# PCBA-2121-01.net
KiCad netlist of a schematic drawn in Altium Designer
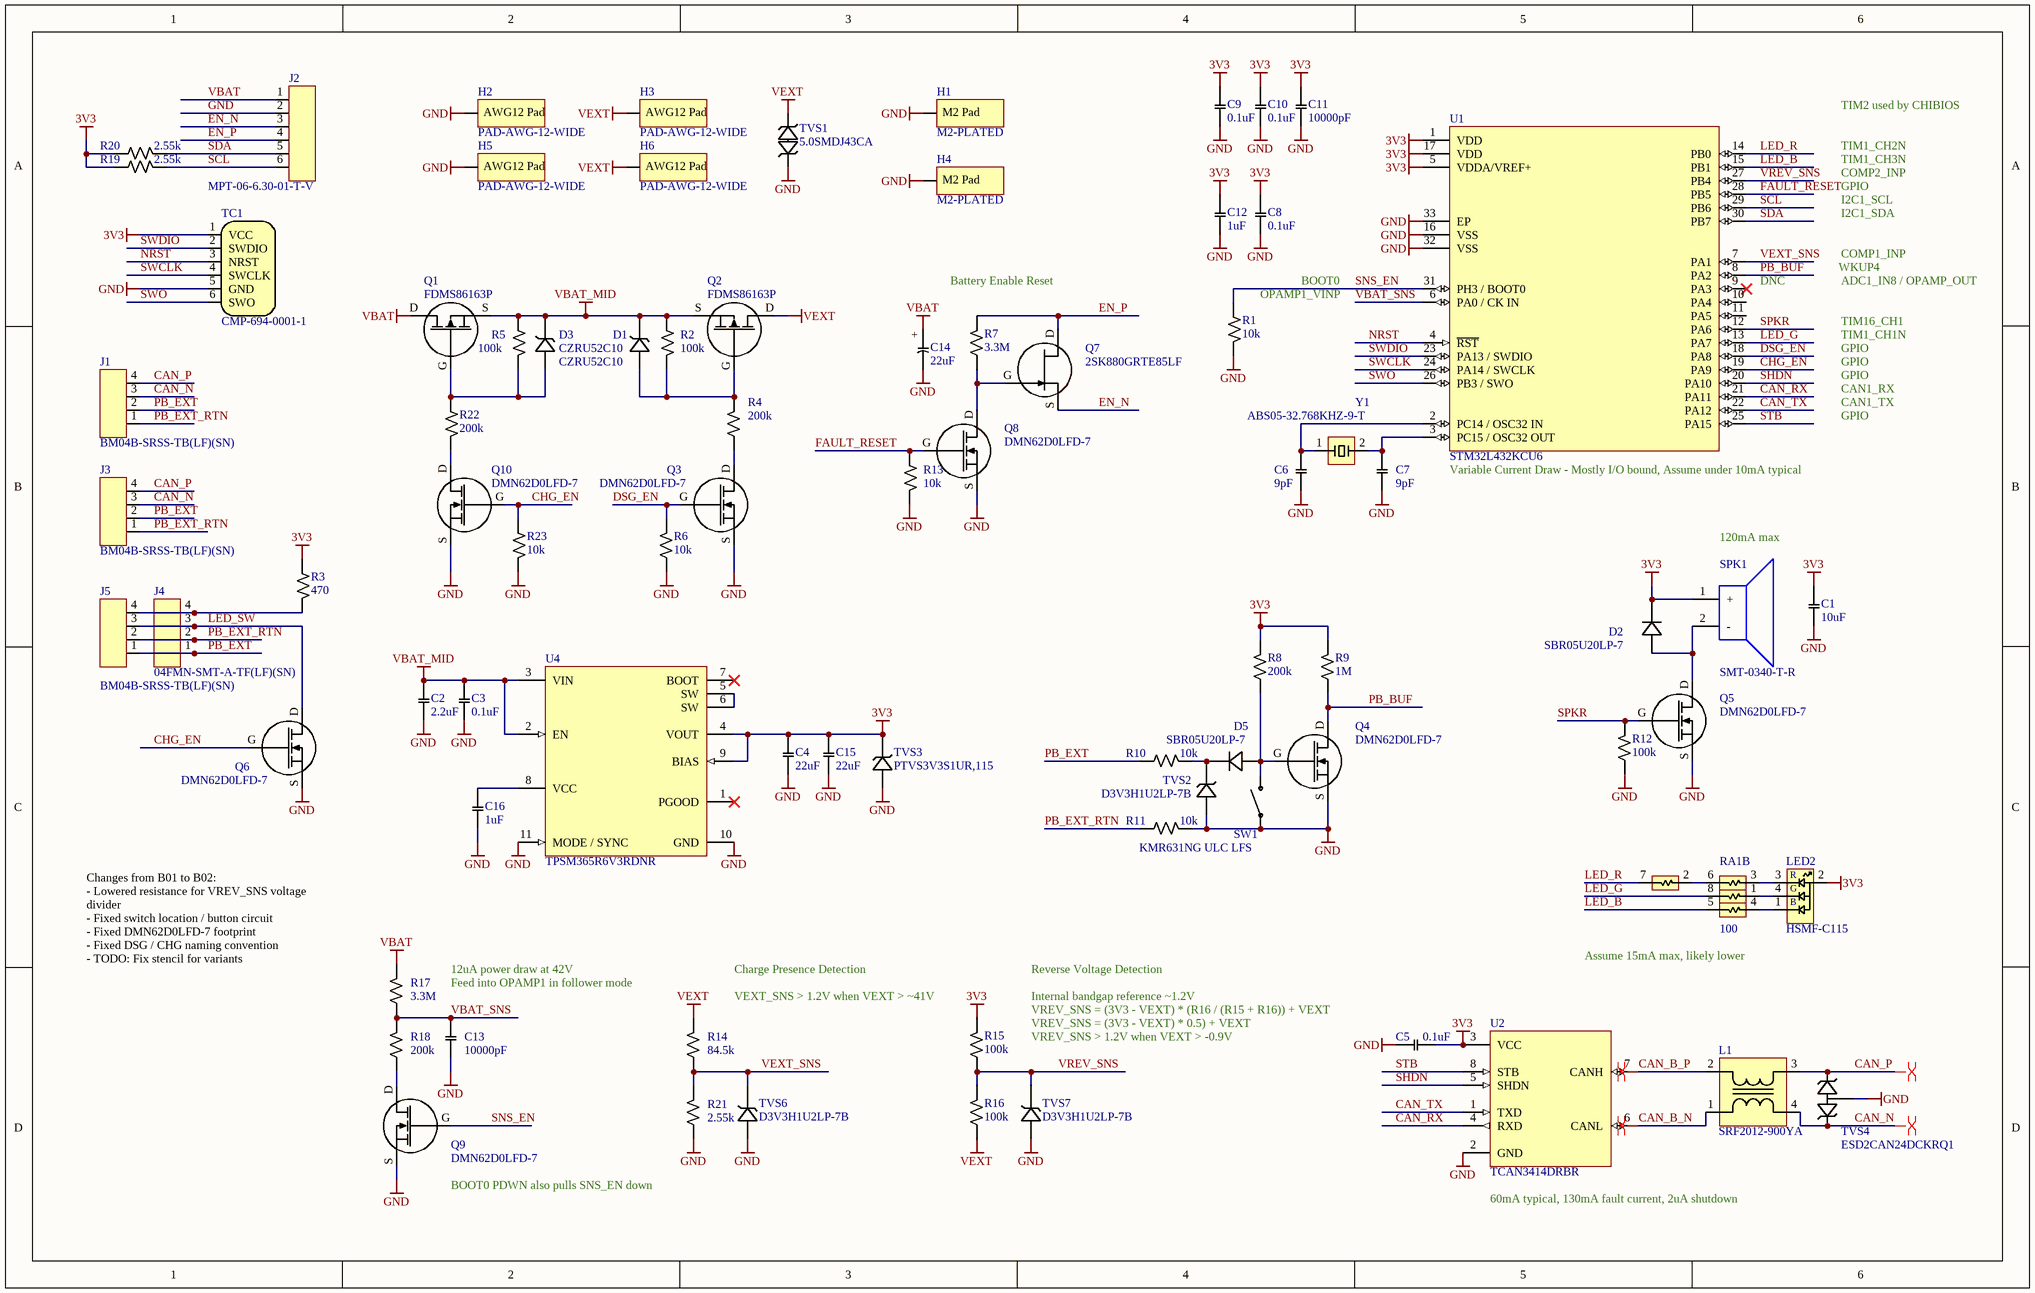
[diagram p0: PCBA-2121-01.SchDoc]

(export (version "E")
  (design (tool "Eeschema 10.0.6"))
  (components
    (comp (ref "C1")
      (value "C-10uf-X5R-16V-10%-0603")
      (footprint "C0603")
      (description "Capacitor Ceramic 10uF 16V X5R 10% SMD 0603")
      (fields (field (name "CAPACITANCE") "10uF") (field (name "TOLERANCE") "10%"))
      (libsource (lib "Hebi Robotics") (part "Capacitor"))
    )
    (comp (ref "C2")
      (value "C-2.2uf-X7R-100V-10%-1206")
      (footprint "C1206")
      (description "Capacitor Ceramic 2.2uF 100V X7R 10% SMD 1206")
      (fields (field (name "CAPACITANCE") "2.2uF") (field (name "TOLERANCE") "±10%"))
      (libsource (lib "Hebi Robotics") (part "Capacitor"))
    )
    (comp (ref "C3")
      (value "C-0.1uf-X7R-100V-10%-0603")
      (footprint "C0603")
      (description "Capacitor Ceramic 0.1uF 100V X7R 10% SMD 0603")
      (fields (field (name "CAPACITANCE") "0.1uF") (field (name "TOLERANCE") "±10%"))
      (libsource (lib "Hebi Robotics") (part "Capacitor"))
    )
    (comp (ref "C4")
      (value "C-22uf-X5R-25V-20%-1206")
      (footprint "C1206")
      (description "Capacitor Ceramic 22uF 25V X5R 20% SMD 1206")
      (fields (field (name "CAPACITANCE") "22uF") (field (name "TOLERANCE") "20%"))
      (libsource (lib "Hebi Robotics") (part "Capacitor"))
    )
    (comp (ref "C5")
      (value "C-0.1uf-X7R-25V-10%-0402")
      (footprint "C0402")
      (description "Capacitor Ceramic 0.1uF 25V X7R 10% SMD 0402")
      (fields (field (name "CAPACITANCE") "0.1uF") (field (name "TOLERANCE") "10%"))
      (libsource (lib "Hebi Robotics") (part "Capacitor"))
    )
    (comp (ref "C6")
      (value "C-9pf-NP0-50V-0.1pF-0402")
      (footprint "C0402")
      (description "Capacitor Ceramic 9pF 50V NP0 ±0.1pF SMD 0402")
      (fields (field (name "CAPACITANCE") "9pF") (field (name "TOLERANCE") "±0.1pF"))
      (libsource (lib "Hebi Robotics") (part "Capacitor"))
    )
    (comp (ref "C7")
      (value "C-9pf-NP0-50V-0.1pF-0402")
      (footprint "C0402")
      (description "Capacitor Ceramic 9pF 50V NP0 ±0.1pF SMD 0402")
      (fields (field (name "CAPACITANCE") "9pF") (field (name "TOLERANCE") "±0.1pF"))
      (libsource (lib "Hebi Robotics") (part "Capacitor"))
    )
    (comp (ref "C8")
      (value "C-0.1uf-X7R-25V-10%-0402")
      (footprint "C0402")
      (description "Capacitor Ceramic 0.1uF 25V X7R 10% SMD 0402")
      (fields (field (name "CAPACITANCE") "0.1uF") (field (name "TOLERANCE") "10%"))
      (libsource (lib "Hebi Robotics") (part "Capacitor"))
    )
    (comp (ref "C9")
      (value "C-0.1uf-X7R-25V-10%-0402")
      (footprint "C0402")
      (description "Capacitor Ceramic 0.1uF 25V X7R 10% SMD 0402")
      (fields (field (name "CAPACITANCE") "0.1uF") (field (name "TOLERANCE") "10%"))
      (libsource (lib "Hebi Robotics") (part "Capacitor"))
    )
    (comp (ref "C10")
      (value "C-0.1uf-X7R-25V-10%-0402")
      (footprint "C0402")
      (description "Capacitor Ceramic 0.1uF 25V X7R 10% SMD 0402")
      (fields (field (name "CAPACITANCE") "0.1uF") (field (name "TOLERANCE") "10%"))
      (libsource (lib "Hebi Robotics") (part "Capacitor"))
    )
    (comp (ref "C11")
      (value "C-10000pf-X7R-50V-10%-0402")
      (footprint "C0402")
      (description "Capacitor Ceramic 10000pF 50V X7R 10% SMD 0402")
      (fields (field (name "TOLERANCE") "10%") (field (name "CAPACITANCE") "10000pF"))
      (libsource (lib "Hebi Robotics") (part "Capacitor"))
    )
    (comp (ref "C12")
      (value "C-1uf-X5R-25V-10%-0402")
      (footprint "C0402")
      (description "Capacitor Ceramic 1uF 25V X5R 10% SMD 0402")
      (fields (field (name "CAPACITANCE") "1uF") (field (name "TOLERANCE") "±10%"))
      (libsource (lib "Hebi Robotics") (part "Capacitor"))
    )
    (comp (ref "C13")
      (value "C-10000pf-X7R-50V-10%-0402")
      (footprint "C0402")
      (description "Capacitor Ceramic 10000pF 50V X7R 10% SMD 0402")
      (fields (field (name "CAPACITANCE") "10000pF") (field (name "TOLERANCE") "10%"))
      (libsource (lib "Hebi Robotics") (part "Capacitor"))
    )
    (comp (ref "C14")
      (value "UCM1H220MCL1GS")
      (footprint "CAPAE5753X61L")
      (description "CAP ALUM 22UF 20% 50V SMD")
      (fields
        (field (name "CAPACITANCE") "22uF")
        (field (name "TOLERANCE") "20%")
        (field (name "VOLTAGE") "50V")
      )
      (libsource (lib "Hebi Robotics") (part "Capacitor_Polarized"))
    )
    (comp (ref "C15")
      (value "C-22uf-X5R-25V-20%-1206")
      (footprint "C1206")
      (description "Capacitor Ceramic 22uF 25V X5R 20% SMD 1206")
      (fields (field (name "CAPACITANCE") "22uF") (field (name "TOLERANCE") "20%"))
      (libsource (lib "Hebi Robotics") (part "Capacitor"))
    )
    (comp (ref "C16")
      (value "C-1uf-X5R-25V-10%-0402")
      (footprint "C0402")
      (description "Capacitor Ceramic 1uF 25V X5R 10% SMD 0402")
      (fields (field (name "CAPACITANCE") "1uF") (field (name "TOLERANCE") "±10%"))
      (libsource (lib "Hebi Robotics") (part "Capacitor"))
    )
    (comp (ref "D1")
      (value "CZRU52C10")
      (footprint "CZRU52C10")
      (description "DIODE ZENER 10V 150MW 0603")
      (libsource (lib "Hebi Robotics") (part "ZENER"))
    )
    (comp (ref "D2")
      (value "SBR05U20LP-7")
      (footprint "DFN1006-2_DIODES")
      (description "DIODE SBR 20V 500MA 2DFN")
      (libsource (lib "Hebi Robotics") (part "DIODE"))
    )
    (comp (ref "D3")
      (value "CZRU52C10")
      (footprint "CZRU52C10")
      (description "DIODE ZENER 10V 150MW 0603")
      (libsource (lib "Hebi Robotics") (part "ZENER"))
    )
    (comp (ref "D5")
      (value "SBR05U20LP-7")
      (footprint "DFN1006-2_DIODES")
      (description "DIODE SBR 20V 500MA 2DFN")
      (libsource (lib "Hebi Robotics") (part "DIODE"))
    )
    (comp (ref "H1")
      (value "M2-PLATED")
      (footprint "M2-PLATED-NORMAL")
      (description "M2 Size Screw Hole, Normal Fit, Plated")
      (libsource (lib "Hebi Robotics") (part "MOUNTING_HOLE"))
    )
    (comp (ref "H2")
      (value "PAD-AWG-12-WIDE")
      (footprint "AWG-12-With-Wire")
      (description "AWG 12 Hole with Wider Pad")
      (libsource (lib "Hebi Robotics") (part "WIRE_PAD"))
    )
    (comp (ref "H3")
      (value "PAD-AWG-12-WIDE")
      (footprint "AWG-12-With-Wire")
      (description "AWG 12 Hole with Wider Pad")
      (libsource (lib "Hebi Robotics") (part "WIRE_PAD"))
    )
    (comp (ref "H4")
      (value "M2-PLATED")
      (footprint "M2-PLATED-NORMAL")
      (description "M2 Size Screw Hole, Normal Fit, Plated")
      (libsource (lib "Hebi Robotics") (part "MOUNTING_HOLE"))
    )
    (comp (ref "H5")
      (value "PAD-AWG-12-WIDE")
      (footprint "AWG-12-With-Wire")
      (description "AWG 12 Hole with Wider Pad")
      (libsource (lib "Hebi Robotics") (part "WIRE_PAD"))
    )
    (comp (ref "H6")
      (value "PAD-AWG-12-WIDE")
      (footprint "AWG-12-With-Wire")
      (description "AWG 12 Hole with Wider Pad")
      (libsource (lib "Hebi Robotics") (part "WIRE_PAD"))
    )
    (comp (ref "J1")
      (value "BM04B-SRSS-TB(LF)(SN)")
      (footprint "BM04B-SRSS-TB")
      (description "CONN HEADER SH 4POS TOP 1MM TIN")
      (fields (field (name "MANUFACTURER") "JST Sales America Inc"))
      (libsource (lib "Hebi Robotics") (part "CONN_1_ROW_004_POS"))
    )
    (comp (ref "J2")
      (value "MPT-06-6.30-01-T-V")
      (footprint "MPT-06-6.30-01-T-V-Footprint-1")
      (description "5.00 MM POWERSTRIP/30 A DUAL BL")
      (libsource (lib "Hebi Robotics") (part "CONN_1_ROW_006_POS"))
    )
    (comp (ref "J3")
      (value "BM04B-SRSS-TB(LF)(SN)")
      (footprint "BM04B-SRSS-TB")
      (description "CONN HEADER SH 4POS TOP 1MM TIN")
      (fields (field (name "MANUFACTURER") "JST Sales America Inc"))
      (libsource (lib "Hebi Robotics") (part "CONN_1_ROW_004_POS"))
    )
    (comp (ref "J4")
      (value "04FMN-SMT-A-TF(LF)(SN)")
      (footprint "04FMN-SMT-A-TF(LF)(SN)-Footprint-1")
      (description "Ffc / Fpc Board Connector, Fmn Series, Surface Mount, Receptacle, 4, 1 Mm Rohs Compliant: Yes")
      (libsource (lib "Hebi Robotics") (part "CONN_1_ROW_004_POS"))
    )
    (comp (ref "J5")
      (value "BM04B-SRSS-TB(LF)(SN)")
      (footprint "BM04B-SRSS-TB")
      (description "CONN HEADER SH 4POS TOP 1MM TIN")
      (fields (field (name "MANUFACTURER") "JST Sales America Inc"))
      (libsource (lib "Hebi Robotics") (part "CONN_1_ROW_004_POS"))
    )
    (comp (ref "L1")
      (value "SRF2012-900YA")
      (footprint "FP-SRF2012A-MFG")
      (description "CMC 400MA 2LN 90 OHM SMD")
      (libsource (lib "Hebi Robotics") (part "CM_CHOKE_4PIN"))
    )
    (comp (ref "LED2")
      (value "HSMF-C115")
      (footprint "HSMF-C115")
      (description "LED RGB DIFFUSED CHIP SMD R/A")
      (libsource (lib "Hebi Robotics") (part "HSMF-C115"))
    )
    (comp (ref "Q1")
      (value "FDMS86163P")
      (footprint "FDMS86300DC")
      (description "MOSFET P-CH 100V 7.9A POWER56")
      (libsource (lib "Hebi Robotics") (part "P_MOSFET"))
    )
    (comp (ref "Q2")
      (value "FDMS86163P")
      (footprint "FDMS86300DC")
      (description "MOSFET P-CH 100V 7.9A POWER56")
      (libsource (lib "Hebi Robotics") (part "P_MOSFET"))
    )
    (comp (ref "Q3")
      (value "DMN62D0LFD-7")
      (footprint "DMN62D0LFD-7-Footprint-1")
      (description "MOSFET N-CH 60V 310MA 3DFN")
      (libsource (lib "Hebi Robotics") (part "N_MOSFET"))
    )
    (comp (ref "Q4")
      (value "DMN62D0LFD-7")
      (footprint "DMN62D0LFD-7-Footprint-1")
      (description "MOSFET N-CH 60V 310MA 3DFN")
      (libsource (lib "Hebi Robotics") (part "N_MOSFET"))
    )
    (comp (ref "Q5")
      (value "DMN62D0LFD-7")
      (footprint "DMN62D0LFD-7-Footprint-1")
      (description "MOSFET N-CH 60V 310MA 3DFN")
      (libsource (lib "Hebi Robotics") (part "N_MOSFET"))
    )
    (comp (ref "Q6")
      (value "DMN62D0LFD-7")
      (footprint "DMN62D0LFD-7-Footprint-1")
      (description "MOSFET N-CH 60V 310MA 3DFN")
      (libsource (lib "Hebi Robotics") (part "N_MOSFET"))
    )
    (comp (ref "Q7")
      (value "2SK880GRTE85LF")
      (footprint "SOT65P205X100-3L")
      (description "JFET N-CH 50V SC70")
      (libsource (lib "Hebi Robotics") (part "N_JFET"))
    )
    (comp (ref "Q8")
      (value "DMN62D0LFD-7")
      (footprint "DMN62D0LFD-7-Footprint-1")
      (description "MOSFET N-CH 60V 310MA 3DFN")
      (libsource (lib "Hebi Robotics") (part "N_MOSFET"))
    )
    (comp (ref "Q9")
      (value "DMN62D0LFD-7")
      (footprint "DMN62D0LFD-7-Footprint-1")
      (description "MOSFET N-CH 60V 310MA 3DFN")
      (libsource (lib "Hebi Robotics") (part "N_MOSFET"))
    )
    (comp (ref "Q10")
      (value "DMN62D0LFD-7")
      (footprint "DMN62D0LFD-7-Footprint-1")
      (description "MOSFET N-CH 60V 310MA 3DFN")
      (libsource (lib "Hebi Robotics") (part "N_MOSFET"))
    )
    (comp (ref "R1")
      (value "R-10k-1%-0.063w-0402")
      (footprint "R0402")
      (description "Resistor 0402 10k Ohm 1% 1-16 Watt")
      (fields
        (field (name "POWER") "0.063W, 1/16W")
        (field (name "RESISTANCE") "10k")
        (field (name "TOLERANCE") "1%")
      )
      (libsource (lib "Hebi Robotics") (part "Resistor"))
    )
    (comp (ref "R2")
      (value "R-100k-1%-0.063w-0402")
      (footprint "R0402")
      (description "Resistor 0402 100k Ohm 1% 1-16 Watt")
      (fields
        (field (name "POWER") "0.063W, 1/16W")
        (field (name "RESISTANCE") "100k")
        (field (name "TOLERANCE") "1%")
      )
      (libsource (lib "Hebi Robotics") (part "Resistor"))
    )
    (comp (ref "R3")
      (value "R-470-1%-0.063w-0402")
      (footprint "R0402")
      (description "Resistor 0402 470 Ohm 1% 1-16 Watt")
      (fields
        (field (name "POWER") "0.063W, 1/16W")
        (field (name "TOLERANCE") "1%")
        (field (name "RESISTANCE") "470")
      )
      (libsource (lib "Hebi Robotics") (part "Resistor"))
    )
    (comp (ref "R4")
      (value "R-200k-1%-0.063w-0402")
      (footprint "R0402")
      (description "Resistor 0402 200k Ohm 1% 1-16 Watt")
      (fields
        (field (name "POWER") "0.063W, 1/16W")
        (field (name "RESISTANCE") "200k")
        (field (name "TOLERANCE") "1%")
      )
      (libsource (lib "Hebi Robotics") (part "Resistor"))
    )
    (comp (ref "R5")
      (value "R-100k-1%-0.063w-0402")
      (footprint "R0402")
      (description "Resistor 0402 100k Ohm 1% 1-16 Watt")
      (fields
        (field (name "POWER") "0.063W, 1/16W")
        (field (name "RESISTANCE") "100k")
        (field (name "TOLERANCE") "1%")
      )
      (libsource (lib "Hebi Robotics") (part "Resistor"))
    )
    (comp (ref "R6")
      (value "R-10k-1%-0.063w-0402")
      (footprint "R0402")
      (description "Resistor 0402 10k Ohm 1% 1-16 Watt")
      (fields
        (field (name "POWER") "0.063W, 1/16W")
        (field (name "RESISTANCE") "10k")
        (field (name "TOLERANCE") "1%")
      )
      (libsource (lib "Hebi Robotics") (part "Resistor"))
    )
    (comp (ref "R7")
      (value "R-3.3M-1%-0.063w-0402")
      (footprint "R0402")
      (description "Resistor 0402 3.3M Ohm 1% 1-16 Watt")
      (fields (field (name "POWER") "0.063W, 1/16W") (field (name "RESISTANCE") "3.3M"))
      (libsource (lib "Hebi Robotics") (part "Resistor"))
    )
    (comp (ref "R8")
      (value "R-200k-1%-0.063w-0402")
      (footprint "R0402")
      (description "Resistor 0402 200k Ohm 1% 1-16 Watt")
      (fields
        (field (name "RESISTANCE") "200k")
        (field (name "POWER") "0.063W, 1/16W")
        (field (name "TOLERANCE") "1%")
      )
      (libsource (lib "Hebi Robotics") (part "Resistor"))
    )
    (comp (ref "R9")
      (value "R-1M-1%-0.063w-0402")
      (footprint "R0402")
      (description "Resistor 0402 1M Ohm 1% 1-16 Watt")
      (fields
        (field (name "RESISTANCE") "1M")
        (field (name "POWER") "0.063W, 1/16W")
        (field (name "TOLERANCE") "1%")
      )
      (libsource (lib "Hebi Robotics") (part "Resistor"))
    )
    (comp (ref "R10")
      (value "R-10k-1%-0.063w-0402")
      (footprint "R0402")
      (description "Resistor 0402 10k Ohm 1% 1-16 Watt")
      (fields
        (field (name "POWER") "0.063W, 1/16W")
        (field (name "RESISTANCE") "10k")
        (field (name "TOLERANCE") "1%")
      )
      (libsource (lib "Hebi Robotics") (part "Resistor"))
    )
    (comp (ref "R11")
      (value "R-10k-1%-0.063w-0402")
      (footprint "R0402")
      (description "Resistor 0402 10k Ohm 1% 1-16 Watt")
      (fields
        (field (name "POWER") "0.063W, 1/16W")
        (field (name "RESISTANCE") "10k")
        (field (name "TOLERANCE") "1%")
      )
      (libsource (lib "Hebi Robotics") (part "Resistor"))
    )
    (comp (ref "R12")
      (value "R-100k-1%-0.063w-0402")
      (footprint "R0402")
      (description "Resistor 0402 100k Ohm 1% 1-16 Watt")
      (fields
        (field (name "POWER") "0.063W, 1/16W")
        (field (name "TOLERANCE") "1%")
        (field (name "RESISTANCE") "100k")
      )
      (libsource (lib "Hebi Robotics") (part "Resistor"))
    )
    (comp (ref "R13")
      (value "R-10k-1%-0.063w-0402")
      (footprint "R0402")
      (description "Resistor 0402 10k Ohm 1% 1-16 Watt")
      (fields
        (field (name "POWER") "0.063W, 1/16W")
        (field (name "RESISTANCE") "10k")
        (field (name "TOLERANCE") "1%")
      )
      (libsource (lib "Hebi Robotics") (part "Resistor"))
    )
    (comp (ref "R14")
      (value "R-84.5k-1%-0.063w-0402")
      (footprint "R0402")
      (description "Resistor 0402 84.5k Ohm 1% 1-16 Watt")
      (fields (field (name "RESISTANCE") "84.5k") (field (name "POWER") "0.063W, 1/16W"))
      (libsource (lib "Hebi Robotics") (part "Resistor"))
    )
    (comp (ref "R15")
      (value "R-100k-1%-0.063w-0402")
      (footprint "R0402")
      (description "Resistor 0402 100k Ohm 1% 1-16 Watt")
      (fields
        (field (name "POWER") "0.063W, 1/16W")
        (field (name "RESISTANCE") "100k")
        (field (name "TOLERANCE") "1%")
      )
      (libsource (lib "Hebi Robotics") (part "Resistor"))
    )
    (comp (ref "R16")
      (value "R-100k-1%-0.063w-0402")
      (footprint "R0402")
      (description "Resistor 0402 100k Ohm 1% 1-16 Watt")
      (fields
        (field (name "POWER") "0.063W, 1/16W")
        (field (name "RESISTANCE") "100k")
        (field (name "TOLERANCE") "1%")
      )
      (libsource (lib "Hebi Robotics") (part "Resistor"))
    )
    (comp (ref "R17")
      (value "R-3.3M-1%-0.063w-0402")
      (footprint "R0402")
      (description "Resistor 0402 3.3M Ohm 1% 1-16 Watt")
      (fields (field (name "POWER") "0.063W, 1/16W") (field (name "RESISTANCE") "3.3M"))
      (libsource (lib "Hebi Robotics") (part "Resistor"))
    )
    (comp (ref "R18")
      (value "R-200k-1%-0.063w-0402")
      (footprint "R0402")
      (description "Resistor 0402 200k Ohm 1% 1-16 Watt")
      (fields
        (field (name "POWER") "0.063W, 1/16W")
        (field (name "RESISTANCE") "200k")
        (field (name "TOLERANCE") "1%")
      )
      (libsource (lib "Hebi Robotics") (part "Resistor"))
    )
    (comp (ref "R19")
      (value "R-2.55k-1%-0.063w-0402")
      (footprint "R0402")
      (description "Resistor 0402 2.55k Ohm 1% 1-16 Watt")
      (fields (field (name "RESISTANCE") "2.55k") (field (name "POWER") "0.063W, 1/16W"))
      (libsource (lib "Hebi Robotics") (part "Resistor"))
    )
    (comp (ref "R20")
      (value "R-2.55k-1%-0.063w-0402")
      (footprint "R0402")
      (description "Resistor 0402 2.55k Ohm 1% 1-16 Watt")
      (fields (field (name "RESISTANCE") "2.55k") (field (name "POWER") "0.063W, 1/16W"))
      (libsource (lib "Hebi Robotics") (part "Resistor"))
    )
    (comp (ref "R21")
      (value "R-2.55k-1%-0.063w-0402")
      (footprint "R0402")
      (description "Resistor 0402 2.55k Ohm 1% 1-16 Watt")
      (fields (field (name "POWER") "0.063W, 1/16W") (field (name "RESISTANCE") "2.55k"))
      (libsource (lib "Hebi Robotics") (part "Resistor"))
    )
    (comp (ref "R22")
      (value "R-200k-1%-0.063w-0402")
      (footprint "R0402")
      (description "Resistor 0402 200k Ohm 1% 1-16 Watt")
      (fields
        (field (name "POWER") "0.063W, 1/16W")
        (field (name "RESISTANCE") "200k")
        (field (name "TOLERANCE") "1%")
      )
      (libsource (lib "Hebi Robotics") (part "Resistor"))
    )
    (comp (ref "R23")
      (value "R-10k-1%-0.063w-0402")
      (footprint "R0402")
      (description "Resistor 0402 10k Ohm 1% 1-16 Watt")
      (fields
        (field (name "POWER") "0.063W, 1/16W")
        (field (name "RESISTANCE") "10k")
        (field (name "TOLERANCE") "1%")
      )
      (libsource (lib "Hebi Robotics") (part "Resistor"))
    )
    (comp (ref "RA1")
      (value "RA-4-C-100-5%-0.063w-0804")
      (footprint "741C083")
      (description "100 ohm Resistor Array 4 Element Concave 5%  1-16Watt 0804")
      (fields (field (name "POWER") "0.063W") (field (name "RESISTANCE") "100"))
      (libsource (lib "Hebi Robotics") (part "RA4"))
    )
    (comp (ref "SPK1")
      (value "SMT-0340-T-R")
      (footprint "SMT-0340-T-R")
      (description "BUZZER MAGNETIC 3V 3.2X3.2MM SMD")
      (fields (field (name "VOLTAGE") "3V"))
      (libsource (lib "Hebi Robotics") (part "Speaker"))
    )
    (comp (ref "SW1")
      (value "KMR631NG ULC LFS")
      (footprint "KMR6_CK")
      (description "SWITCH TACTILE SPST-NO 50MA 32V")
      (fields (field (name "MANUFACTURER") "ITT C&K"))
      (libsource (lib "Hebi Robotics") (part "SPST_NO"))
    )
    (comp (ref "TC1")
      (value "CMP-694-0001-1")
      (footprint "TC2030-MCP-NL_SMALL")
      (description "TC2030-MCP-NL")
      (fields (field (name "MANUFACTURER PART NUMBER") "TC2030-MCP-NL_SMALL"))
      (libsource (lib "Hebi Robotics") (part "TC2030-MCP-NL"))
    )
    (comp (ref "TVS1")
      (value "5.0SMDJ43CA")
      (footprint "DIOM6959X26L")
      (description "TVS DIODE 43VWM 69.4VC DO214AB")
      (libsource (lib "Hebi Robotics") (part "TVS_BI"))
    )
    (comp (ref "TVS2")
      (value "D3V3H1U2LP-7B")
      (footprint "DFN70P101X53-2N")
      (description "TVS DIODE 3.3V 10V DFN1006-2")
      (libsource (lib "Hebi Robotics") (part "TVS"))
    )
    (comp (ref "TVS3")
      (value "PTVS3V3S1UR,115")
      (footprint "SOD-123W_NXP")
      (description "TVS DIODE 3.3VWM 8VC SOD123W")
      (libsource (lib "Hebi Robotics") (part "TVS"))
    )
    (comp (ref "TVS4")
      (value "ESD2CAN24DCKRQ1")
      (footprint "SOT65P210X90-3L")
      (description "TVS DIODE 24VWM 37VC CAN SC703")
      (libsource (lib "Hebi Robotics") (part "ESD2CAN24DCKRQ1-Symbol-1"))
    )
    (comp (ref "TVS6")
      (value "D3V3H1U2LP-7B")
      (footprint "DFN70P101X53-2N")
      (description "TVS DIODE 3.3V 10V DFN1006-2")
      (libsource (lib "Hebi Robotics") (part "TVS"))
    )
    (comp (ref "TVS7")
      (value "D3V3H1U2LP-7B")
      (footprint "DFN70P101X53-2N")
      (description "TVS DIODE 3.3V 10V DFN1006-2")
      (libsource (lib "Hebi Robotics") (part "TVS"))
    )
    (comp (ref "U1")
      (value "STM32L432KCU6")
      (footprint "QFN50P500X500X60_HS-33L")
      (description "IC MCU 32BIT 256KB FLSH 32UFQFPN")
      (libsource (lib "Hebi Robotics") (part "STM32L412K8U6"))
    )
    (comp (ref "U2")
      (value "TCAN3414DRBR")
      (footprint "SON65P300X100_HS-9L")
      (description "IC TRANSCEIVER HALF 1/1 8SON")
      (libsource (lib "Hebi Robotics") (part "TCAN3414DRBR-Symbol-1"))
    )
    (comp (ref "U4")
      (value "TPSM365R6V3RDNR")
      (footprint "TPSM365R6V3RDNR-Footprint-1")
      (description "3-V TO 65-V INPUT, 3V3 OUT, 300mA")
      (libsource (lib "Hebi Robotics") (part "TPSM365R6V3RDNR-Symbol-1"))
    )
    (comp (ref "Y1")
      (value "ABS05-32.768KHZ-9-T")
      (footprint "ABS05-32.768KHZ-9-T-Footprint-1")
      (description "CRYSTAL 32.7680KHZ 9PF SMD")
      (libsource (lib "Hebi Robotics") (part "CRYSTAL"))
    )
  )
  (nets
    (net (code "1") (name "/CAN_B_N") (class "Default")
      (node (ref "L1") (pin "1") (pinfunction "1_1") (pintype "passive"))
      (node (ref "U2") (pin "6") (pinfunction "CANL_6") (pintype "bidirectional"))
    )
    (net (code "2") (name "/CAN_B_P") (class "Default")
      (node (ref "L1") (pin "2") (pinfunction "2_2") (pintype "passive"))
      (node (ref "U2") (pin "7") (pinfunction "CANH_7") (pintype "bidirectional"))
    )
    (net (code "3") (name "/CAN_N") (class "Default")
      (node (ref "J1") (pin "3") (pinfunction "3_3") (pintype "passive"))
      (node (ref "J3") (pin "3") (pinfunction "3_3") (pintype "passive"))
      (node (ref "L1") (pin "4") (pinfunction "4_4") (pintype "passive"))
      (node (ref "TVS4") (pin "2") (pinfunction "2_2") (pintype "passive"))
    )
    (net (code "4") (name "/CAN_P") (class "Default")
      (node (ref "J1") (pin "4") (pinfunction "4_4") (pintype "passive"))
      (node (ref "J3") (pin "4") (pinfunction "4_4") (pintype "passive"))
      (node (ref "L1") (pin "3") (pinfunction "3_3") (pintype "passive"))
      (node (ref "TVS4") (pin "1") (pinfunction "1_1") (pintype "passive"))
    )
    (net (code "5") (name "/CAN_RX") (class "Default")
      (node (ref "U1") (pin "21") (pinfunction "PA11_21") (pintype "bidirectional"))
      (node (ref "U2") (pin "4") (pinfunction "RXD_4") (pintype "output"))
    )
    (net (code "6") (name "/CAN_TX") (class "Default")
      (node (ref "U1") (pin "22") (pinfunction "PA12_22") (pintype "bidirectional"))
      (node (ref "U2") (pin "1") (pinfunction "TXD_1") (pintype "input"))
    )
    (net (code "7") (name "/CHG_EN") (class "Default")
      (node (ref "Q10") (pin "G") (pinfunction "G_G") (pintype "passive"))
      (node (ref "Q6") (pin "G") (pinfunction "G_G") (pintype "passive"))
      (node (ref "R23") (pin "2") (pinfunction "2_2") (pintype "passive"))
      (node (ref "U1") (pin "19") (pinfunction "PA9_19") (pintype "bidirectional"))
    )
    (net (code "8") (name "/DSG_EN") (class "Default")
      (node (ref "Q3") (pin "G") (pinfunction "G_G") (pintype "passive"))
      (node (ref "R6") (pin "2") (pinfunction "2_2") (pintype "passive"))
      (node (ref "U1") (pin "18") (pinfunction "PA8_18") (pintype "bidirectional"))
    )
    (net (code "9") (name "/EN_N") (class "Default")
      (node (ref "J2") (pin "3") (pinfunction "3_3") (pintype "passive"))
      (node (ref "Q7") (pin "S") (pinfunction "S_S") (pintype "passive"))
    )
    (net (code "10") (name "/EN_P") (class "Default")
      (node (ref "J2") (pin "4") (pinfunction "4_4") (pintype "passive"))
      (node (ref "Q7") (pin "D") (pinfunction "D_D") (pintype "passive"))
      (node (ref "R7") (pin "2") (pinfunction "2_2") (pintype "passive"))
    )
    (net (code "11") (name "/FAULT_RESET") (class "Default")
      (node (ref "Q8") (pin "G") (pinfunction "G_G") (pintype "passive"))
      (node (ref "R13") (pin "1") (pinfunction "1_1") (pintype "passive"))
      (node (ref "U1") (pin "28") (pinfunction "PB5_28") (pintype "bidirectional"))
    )
    (net (code "12") (name "/LED_B") (class "Default")
      (node (ref "RA1") (pin "5") (pinfunction "5_5") (pintype "passive"))
      (node (ref "U1") (pin "15") (pinfunction "PB1_15") (pintype "bidirectional"))
    )
    (net (code "13") (name "/LED_G") (class "Default")
      (node (ref "RA1") (pin "8") (pinfunction "8_8") (pintype "passive"))
      (node (ref "U1") (pin "13") (pinfunction "PA7_13") (pintype "bidirectional"))
    )
    (net (code "14") (name "/LED_R") (class "Default")
      (node (ref "RA1") (pin "7") (pinfunction "7_7") (pintype "passive"))
      (node (ref "U1") (pin "14") (pinfunction "PB0_14") (pintype "bidirectional"))
    )
    (net (code "15") (name "/LED_SW") (class "Default")
      (node (ref "J4") (pin "3") (pinfunction "3_3") (pintype "passive"))
      (node (ref "J5") (pin "3") (pinfunction "3_3") (pintype "passive"))
      (node (ref "Q6") (pin "D") (pinfunction "D_D") (pintype "passive"))
    )
    (net (code "16") (name "/NRST") (class "Default")
      (node (ref "TC1") (pin "3") (pinfunction "NRST_3") (pintype "passive"))
      (node (ref "U1") (pin "4") (pinfunction "~{RST}_4") (pintype "input"))
    )
    (net (code "17") (name "/PB_BUF") (class "Default")
      (node (ref "Q4") (pin "D") (pinfunction "D_D") (pintype "passive"))
      (node (ref "R9") (pin "1") (pinfunction "1_1") (pintype "passive"))
      (node (ref "U1") (pin "8") (pinfunction "PA2_8") (pintype "bidirectional"))
    )
    (net (code "18") (name "/PB_EXT") (class "Default")
      (node (ref "J1") (pin "2") (pinfunction "2_2") (pintype "passive"))
      (node (ref "J3") (pin "2") (pinfunction "2_2") (pintype "passive"))
      (node (ref "J4") (pin "1") (pinfunction "1_1") (pintype "passive"))
      (node (ref "J5") (pin "1") (pinfunction "1_1") (pintype "passive"))
      (node (ref "R10") (pin "1") (pinfunction "1_1") (pintype "passive"))
    )
    (net (code "19") (name "/PB_EXT_RTN") (class "Default")
      (node (ref "J1") (pin "1") (pinfunction "1_1") (pintype "passive"))
      (node (ref "J3") (pin "1") (pinfunction "1_1") (pintype "passive"))
      (node (ref "J4") (pin "2") (pinfunction "2_2") (pintype "passive"))
      (node (ref "J5") (pin "2") (pinfunction "2_2") (pintype "passive"))
      (node (ref "R11") (pin "1") (pinfunction "1_1") (pintype "passive"))
    )
    (net (code "20") (name "/SCL") (class "Default")
      (node (ref "J2") (pin "6") (pinfunction "6_6") (pintype "passive"))
      (node (ref "R19") (pin "2") (pinfunction "2_2") (pintype "passive"))
      (node (ref "U1") (pin "29") (pinfunction "PB6_29") (pintype "bidirectional"))
    )
    (net (code "21") (name "/SDA") (class "Default")
      (node (ref "J2") (pin "5") (pinfunction "5_5") (pintype "passive"))
      (node (ref "R20") (pin "2") (pinfunction "2_2") (pintype "passive"))
      (node (ref "U1") (pin "30") (pinfunction "PB7_30") (pintype "bidirectional"))
    )
    (net (code "22") (name "/SHDN") (class "Default")
      (node (ref "U1") (pin "20") (pinfunction "PA10_20") (pintype "bidirectional"))
      (node (ref "U2") (pin "5") (pinfunction "SHDN_5") (pintype "input"))
    )
    (net (code "23") (name "/SNS_EN") (class "Default")
      (node (ref "Q9") (pin "G") (pinfunction "G_G") (pintype "passive"))
      (node (ref "R1") (pin "1") (pinfunction "1_1") (pintype "passive"))
      (node (ref "U1") (pin "31") (pinfunction "PH3_/_BOOT0_31") (pintype "bidirectional"))
    )
    (net (code "24") (name "/SPKR") (class "Default")
      (node (ref "Q5") (pin "G") (pinfunction "G_G") (pintype "passive"))
      (node (ref "R12") (pin "2") (pinfunction "2_2") (pintype "passive"))
      (node (ref "U1") (pin "12") (pinfunction "PA6_12") (pintype "bidirectional"))
    )
    (net (code "25") (name "/STB") (class "Default")
      (node (ref "U1") (pin "25") (pinfunction "PA15_25") (pintype "bidirectional"))
      (node (ref "U2") (pin "8") (pinfunction "STB_8") (pintype "input"))
    )
    (net (code "26") (name "/SWCLK") (class "Default")
      (node (ref "TC1") (pin "4") (pinfunction "SWCLK_4") (pintype "passive"))
      (node (ref "U1") (pin "24") (pinfunction "PA14_/_SWCLK_24") (pintype "bidirectional"))
    )
    (net (code "27") (name "/SWDIO") (class "Default")
      (node (ref "TC1") (pin "2") (pinfunction "SWDIO_2") (pintype "passive"))
      (node (ref "U1") (pin "23") (pinfunction "PA13_/_SWDIO_23") (pintype "bidirectional"))
    )
    (net (code "28") (name "/SWO") (class "Default")
      (node (ref "TC1") (pin "6") (pinfunction "SWO_6") (pintype "passive"))
      (node (ref "U1") (pin "26") (pinfunction "PB3_/_SWO_26") (pintype "bidirectional"))
    )
    (net (code "29") (name "/VBAT_SNS") (class "Default")
      (node (ref "C13") (pin "1") (pinfunction "1_1") (pintype "passive"))
      (node (ref "R17") (pin "1") (pinfunction "1_1") (pintype "passive"))
      (node (ref "R18") (pin "2") (pinfunction "2_2") (pintype "passive"))
      (node (ref "U1") (pin "6") (pinfunction "PA0_/_CK_IN_6") (pintype "bidirectional"))
    )
    (net (code "30") (name "/VEXT_SNS") (class "Default")
      (node (ref "R14") (pin "1") (pinfunction "1_1") (pintype "passive"))
      (node (ref "R21") (pin "2") (pinfunction "2_2") (pintype "passive"))
      (node (ref "TVS6") (pin "C") (pinfunction "C_C") (pintype "passive"))
      (node (ref "U1") (pin "7") (pinfunction "PA1_7") (pintype "bidirectional"))
    )
    (net (code "31") (name "/VREV_SNS") (class "Default")
      (node (ref "R15") (pin "1") (pinfunction "1_1") (pintype "passive"))
      (node (ref "R16") (pin "2") (pinfunction "2_2") (pintype "passive"))
      (node (ref "TVS7") (pin "C") (pinfunction "C_C") (pintype "passive"))
      (node (ref "U1") (pin "27") (pinfunction "PB4_27") (pintype "bidirectional"))
    )
    (net (code "32") (name "3V3") (class "Default")
      (node (ref "C1") (pin "1") (pinfunction "1_1") (pintype "passive"))
      (node (ref "C10") (pin "2") (pinfunction "2_2") (pintype "passive"))
      (node (ref "C11") (pin "2") (pinfunction "2_2") (pintype "passive"))
      (node (ref "C12") (pin "1") (pinfunction "1_1") (pintype "passive"))
      (node (ref "C15") (pin "2") (pinfunction "2_2") (pintype "passive"))
      (node (ref "C4") (pin "2") (pinfunction "2_2") (pintype "passive"))
      (node (ref "C5") (pin "2") (pinfunction "2_2") (pintype "passive"))
      (node (ref "C8") (pin "2") (pinfunction "2_2") (pintype "passive"))
      (node (ref "C9") (pin "2") (pinfunction "2_2") (pintype "passive"))
      (node (ref "D2") (pin "C") (pinfunction "C_C") (pintype "passive"))
      (node (ref "LED2") (pin "2") (pinfunction "A_2") (pintype "passive"))
      (node (ref "R15") (pin "2") (pinfunction "2_2") (pintype "passive"))
      (node (ref "R19") (pin "1") (pinfunction "1_1") (pintype "passive"))
      (node (ref "R20") (pin "1") (pinfunction "1_1") (pintype "passive"))
      (node (ref "R3") (pin "1") (pinfunction "1_1") (pintype "passive"))
      (node (ref "R8") (pin "2") (pinfunction "2_2") (pintype "passive"))
      (node (ref "R9") (pin "2") (pinfunction "2_2") (pintype "passive"))
      (node (ref "SPK1") (pin "1") (pinfunction "+_1") (pintype "passive"))
      (node (ref "TC1") (pin "1") (pinfunction "VCC_1") (pintype "passive"))
      (node (ref "TVS3") (pin "C") (pinfunction "C_C") (pintype "passive"))
      (node (ref "U1") (pin "1") (pinfunction "VDD_1") (pintype "power_in"))
      (node (ref "U1") (pin "17") (pinfunction "VDD_17") (pintype "power_in"))
      (node (ref "U1") (pin "5") (pinfunction "VDDA/VREF+_5") (pintype "power_in"))
      (node (ref "U2") (pin "3") (pinfunction "VCC_3") (pintype "power_in"))
      (node (ref "U4") (pin "4") (pinfunction "VOUT_4") (pintype "power_in"))
      (node (ref "U4") (pin "9") (pinfunction "BIAS_9") (pintype "input"))
    )
    (net (code "33") (name "GND") (class "Default")
      (node (ref "C1") (pin "2") (pinfunction "2_2") (pintype "passive"))
      (node (ref "C10") (pin "1") (pinfunction "1_1") (pintype "passive"))
      (node (ref "C11") (pin "1") (pinfunction "1_1") (pintype "passive"))
      (node (ref "C12") (pin "2") (pinfunction "2_2") (pintype "passive"))
      (node (ref "C13") (pin "2") (pinfunction "2_2") (pintype "passive"))
      (node (ref "C14") (pin "-") (pinfunction "-_-") (pintype "passive"))
      (node (ref "C15") (pin "1") (pinfunction "1_1") (pintype "passive"))
      (node (ref "C16") (pin "1") (pinfunction "1_1") (pintype "passive"))
      (node (ref "C2") (pin "1") (pinfunction "1_1") (pintype "passive"))
      (node (ref "C3") (pin "1") (pinfunction "1_1") (pintype "passive"))
      (node (ref "C4") (pin "1") (pinfunction "1_1") (pintype "passive"))
      (node (ref "C5") (pin "1") (pinfunction "1_1") (pintype "passive"))
      (node (ref "C6") (pin "1") (pinfunction "1_1") (pintype "passive"))
      (node (ref "C7") (pin "1") (pinfunction "1_1") (pintype "passive"))
      (node (ref "C8") (pin "1") (pinfunction "1_1") (pintype "passive"))
      (node (ref "C9") (pin "1") (pinfunction "1_1") (pintype "passive"))
      (node (ref "H1") (pin "HOLE") (pinfunction "HOLE_HOLE") (pintype "passive"))
      (node (ref "H2") (pin "HOLE") (pinfunction "HOLE_HOLE") (pintype "passive"))
      (node (ref "H4") (pin "HOLE") (pinfunction "HOLE_HOLE") (pintype "passive"))
      (node (ref "H5") (pin "HOLE") (pinfunction "HOLE_HOLE") (pintype "passive"))
      (node (ref "J2") (pin "2") (pinfunction "2_2") (pintype "passive"))
      (node (ref "Q10") (pin "S") (pinfunction "S_S") (pintype "passive"))
      (node (ref "Q3") (pin "S") (pinfunction "S_S") (pintype "passive"))
      (node (ref "Q4") (pin "S") (pinfunction "S_S") (pintype "passive"))
      (node (ref "Q5") (pin "S") (pinfunction "S_S") (pintype "passive"))
      (node (ref "Q6") (pin "S") (pinfunction "S_S") (pintype "passive"))
      (node (ref "Q8") (pin "S") (pinfunction "S_S") (pintype "passive"))
      (node (ref "Q9") (pin "S") (pinfunction "S_S") (pintype "passive"))
      (node (ref "R1") (pin "2") (pinfunction "2_2") (pintype "passive"))
      (node (ref "R11") (pin "2") (pinfunction "2_2") (pintype "passive"))
      (node (ref "R12") (pin "1") (pinfunction "1_1") (pintype "passive"))
      (node (ref "R13") (pin "2") (pinfunction "2_2") (pintype "passive"))
      (node (ref "R21") (pin "1") (pinfunction "1_1") (pintype "passive"))
      (node (ref "R23") (pin "1") (pinfunction "1_1") (pintype "passive"))
      (node (ref "R6") (pin "1") (pinfunction "1_1") (pintype "passive"))
      (node (ref "SW1") (pin "1") (pinfunction "1_1") (pintype "passive"))
      (node (ref "TC1") (pin "5") (pinfunction "GND_5") (pintype "passive"))
      (node (ref "TVS1") (pin "C") (pinfunction "C_C") (pintype "passive"))
      (node (ref "TVS2") (pin "A") (pinfunction "A_A") (pintype "passive"))
      (node (ref "TVS3") (pin "A") (pinfunction "A_A") (pintype "passive"))
      (node (ref "TVS4") (pin "3") (pinfunction "3_3") (pintype "passive"))
      (node (ref "TVS6") (pin "A") (pinfunction "A_A") (pintype "passive"))
      (node (ref "TVS7") (pin "A") (pinfunction "A_A") (pintype "passive"))
      (node (ref "U1") (pin "16") (pinfunction "VSS_16") (pintype "power_in"))
      (node (ref "U1") (pin "32") (pinfunction "VSS_32") (pintype "power_in"))
      (node (ref "U1") (pin "33") (pinfunction "EP_33") (pintype "power_in"))
      (node (ref "U2") (pin "2") (pinfunction "GND_2") (pintype "passive"))
      (node (ref "U4") (pin "10") (pinfunction "GND_10") (pintype "passive"))
      (node (ref "U4") (pin "11") (pinfunction "MODE_/_SYNC_11") (pintype "input"))
    )
    (net (code "34") (name "Net-(D1-PadA)") (class "Default")
      (node (ref "D1") (pin "A") (pinfunction "A_A") (pintype "passive"))
      (node (ref "Q2") (pin "G") (pinfunction "G_G") (pintype "passive"))
      (node (ref "R2") (pin "2") (pinfunction "2_2") (pintype "passive"))
      (node (ref "R4") (pin "2") (pinfunction "2_2") (pintype "passive"))
    )
    (net (code "35") (name "Net-(D3-PadA)") (class "Default")
      (node (ref "D3") (pin "A") (pinfunction "A_A") (pintype "passive"))
      (node (ref "Q1") (pin "G") (pinfunction "G_G") (pintype "passive"))
      (node (ref "R22") (pin "2") (pinfunction "2_2") (pintype "passive"))
      (node (ref "R5") (pin "2") (pinfunction "2_2") (pintype "passive"))
    )
    (net (code "36") (name "Net-(D5-PadA)") (class "Default")
      (node (ref "D5") (pin "A") (pinfunction "A_A") (pintype "passive"))
      (node (ref "Q4") (pin "G") (pinfunction "G_G") (pintype "passive"))
      (node (ref "R8") (pin "1") (pinfunction "1_1") (pintype "passive"))
      (node (ref "SW1") (pin "2") (pinfunction "2_2") (pintype "passive"))
    )
    (net (code "37") (name "Net-(D5-PadC)") (class "Default")
      (node (ref "D5") (pin "C") (pinfunction "C_C") (pintype "passive"))
      (node (ref "R10") (pin "2") (pinfunction "2_2") (pintype "passive"))
      (node (ref "TVS2") (pin "C") (pinfunction "C_C") (pintype "passive"))
    )
    (net (code "38") (name "Net-(J4-Pad4)") (class "Default")
      (node (ref "J4") (pin "4") (pinfunction "4_4") (pintype "passive"))
      (node (ref "J5") (pin "4") (pinfunction "4_4") (pintype "passive"))
      (node (ref "R3") (pin "2") (pinfunction "2_2") (pintype "passive"))
    )
    (net (code "39") (name "Net-(LED2-CB)") (class "Default")
      (node (ref "LED2") (pin "3") (pinfunction "CB_3") (pintype "passive"))
      (node (ref "RA1") (pin "3") (pinfunction "3_3") (pintype "passive"))
    )
    (net (code "40") (name "Net-(LED2-CG)") (class "Default")
      (node (ref "LED2") (pin "4") (pinfunction "CG_4") (pintype "passive"))
      (node (ref "RA1") (pin "1") (pinfunction "1_1") (pintype "passive"))
    )
    (net (code "41") (name "Net-(LED2-CR)") (class "Default")
      (node (ref "LED2") (pin "1") (pinfunction "CR_1") (pintype "passive"))
      (node (ref "RA1") (pin "4") (pinfunction "4_4") (pintype "passive"))
    )
    (net (code "42") (name "Net-(Q3-PadD)") (class "Default")
      (node (ref "Q3") (pin "D") (pinfunction "D_D") (pintype "passive"))
      (node (ref "R4") (pin "1") (pinfunction "1_1") (pintype "passive"))
    )
    (net (code "43") (name "Net-(Q7-PadG)") (class "Default")
      (node (ref "Q7") (pin "G") (pinfunction "G_G") (pintype "passive"))
      (node (ref "Q8") (pin "D") (pinfunction "D_D") (pintype "passive"))
      (node (ref "R7") (pin "1") (pinfunction "1_1") (pintype "passive"))
    )
    (net (code "44") (name "Net-(Q9-PadD)") (class "Default")
      (node (ref "Q9") (pin "D") (pinfunction "D_D") (pintype "passive"))
      (node (ref "R18") (pin "1") (pinfunction "1_1") (pintype "passive"))
    )
    (net (code "45") (name "Net-(Q10-PadD)") (class "Default")
      (node (ref "Q10") (pin "D") (pinfunction "D_D") (pintype "passive"))
      (node (ref "R22") (pin "1") (pinfunction "1_1") (pintype "passive"))
    )
    (net (code "46") (name "Net-(RA1-Pad2)") (class "Default")
      (node (ref "RA1") (pin "2") (pinfunction "2_2") (pintype "passive"))
      (node (ref "RA1") (pin "6") (pinfunction "6_6") (pintype "passive"))
    )
    (net (code "47") (name "Net-(SPK1--)") (class "Default")
      (node (ref "D2") (pin "A") (pinfunction "A_A") (pintype "passive"))
      (node (ref "Q5") (pin "D") (pinfunction "D_D") (pintype "passive"))
      (node (ref "SPK1") (pin "2") (pinfunction "-_2") (pintype "passive"))
    )
    (net (code "48") (name "Net-(U1-PC14_{slash}_OSC32_IN)") (class "Default")
      (node (ref "C6") (pin "2") (pinfunction "2_2") (pintype "passive"))
      (node (ref "U1") (pin "2") (pinfunction "PC14_/_OSC32_IN_2") (pintype "bidirectional"))
      (node (ref "Y1") (pin "1") (pinfunction "1_1") (pintype "passive"))
    )
    (net (code "49") (name "Net-(U1-PC15_{slash}_OSC32_OUT)") (class "Default")
      (node (ref "C7") (pin "2") (pinfunction "2_2") (pintype "passive"))
      (node (ref "U1") (pin "3") (pinfunction "PC15_/_OSC32_OUT_3") (pintype "bidirectional"))
      (node (ref "Y1") (pin "2") (pinfunction "2_2") (pintype "passive"))
    )
    (net (code "50") (name "Net-(U4-SW-Pad5)") (class "Default")
      (node (ref "U4") (pin "5") (pinfunction "SW_5") (pintype "power_in"))
      (node (ref "U4") (pin "6") (pinfunction "SW_6") (pintype "power_in"))
    )
    (net (code "51") (name "Net-(U4-VCC)") (class "Default")
      (node (ref "C16") (pin "2") (pinfunction "2_2") (pintype "passive"))
      (node (ref "U4") (pin "8") (pinfunction "VCC_8") (pintype "power_in"))
    )
    (net (code "52") (name "VBAT") (class "Default")
      (node (ref "C14") (pin "+") (pinfunction "+_+") (pintype "passive"))
      (node (ref "J2") (pin "1") (pinfunction "1_1") (pintype "passive"))
      (node (ref "Q1") (pin "D") (pinfunction "D_D") (pintype "passive"))
      (node (ref "R17") (pin "2") (pinfunction "2_2") (pintype "passive"))
    )
    (net (code "53") (name "VBAT_MID") (class "Default")
      (node (ref "C2") (pin "2") (pinfunction "2_2") (pintype "passive"))
      (node (ref "C3") (pin "2") (pinfunction "2_2") (pintype "passive"))
      (node (ref "D1") (pin "C") (pinfunction "C_C") (pintype "passive"))
      (node (ref "D3") (pin "C") (pinfunction "C_C") (pintype "passive"))
      (node (ref "Q1") (pin "S") (pinfunction "S_S") (pintype "passive"))
      (node (ref "Q2") (pin "S") (pinfunction "S_S") (pintype "passive"))
      (node (ref "R2") (pin "1") (pinfunction "1_1") (pintype "passive"))
      (node (ref "R5") (pin "1") (pinfunction "1_1") (pintype "passive"))
      (node (ref "U4") (pin "2") (pinfunction "EN_2") (pintype "input"))
      (node (ref "U4") (pin "3") (pinfunction "VIN_3") (pintype "power_in"))
    )
    (net (code "54") (name "VEXT") (class "Default")
      (node (ref "H3") (pin "HOLE") (pinfunction "HOLE_HOLE") (pintype "passive"))
      (node (ref "H6") (pin "HOLE") (pinfunction "HOLE_HOLE") (pintype "passive"))
      (node (ref "Q2") (pin "D") (pinfunction "D_D") (pintype "passive"))
      (node (ref "R14") (pin "2") (pinfunction "2_2") (pintype "passive"))
      (node (ref "R16") (pin "1") (pinfunction "1_1") (pintype "passive"))
      (node (ref "TVS1") (pin "A") (pinfunction "A_A") (pintype "passive"))
    )
    (net (code "55") (name "unconnected-(U1-PA3-Pad9)") (class "Default")
      (node (ref "U1") (pin "9") (pinfunction "PA3_9") (pintype "bidirectional+no_connect"))
    )
    (net (code "56") (name "unconnected-(U1-PA4-Pad10)") (class "Default")
      (node (ref "U1") (pin "10") (pinfunction "PA4_10") (pintype "bidirectional"))
    )
    (net (code "57") (name "unconnected-(U1-PA5-Pad11)") (class "Default")
      (node (ref "U1") (pin "11") (pinfunction "PA5_11") (pintype "bidirectional"))
    )
    (net (code "58") (name "unconnected-(U4-BOOT-Pad7)") (class "Default")
      (node (ref "U4") (pin "7") (pinfunction "BOOT_7") (pintype "power_in+no_connect"))
    )
    (net (code "59") (name "unconnected-(U4-PGOOD-Pad1)") (class "Default")
      (node (ref "U4") (pin "1") (pinfunction "PGOOD_1") (pintype "open_collector+no_connect"))
    )
  )
)
